# DAP-Peripherals-4.net
KiCad netlist of a schematic drawn in Altium Designer
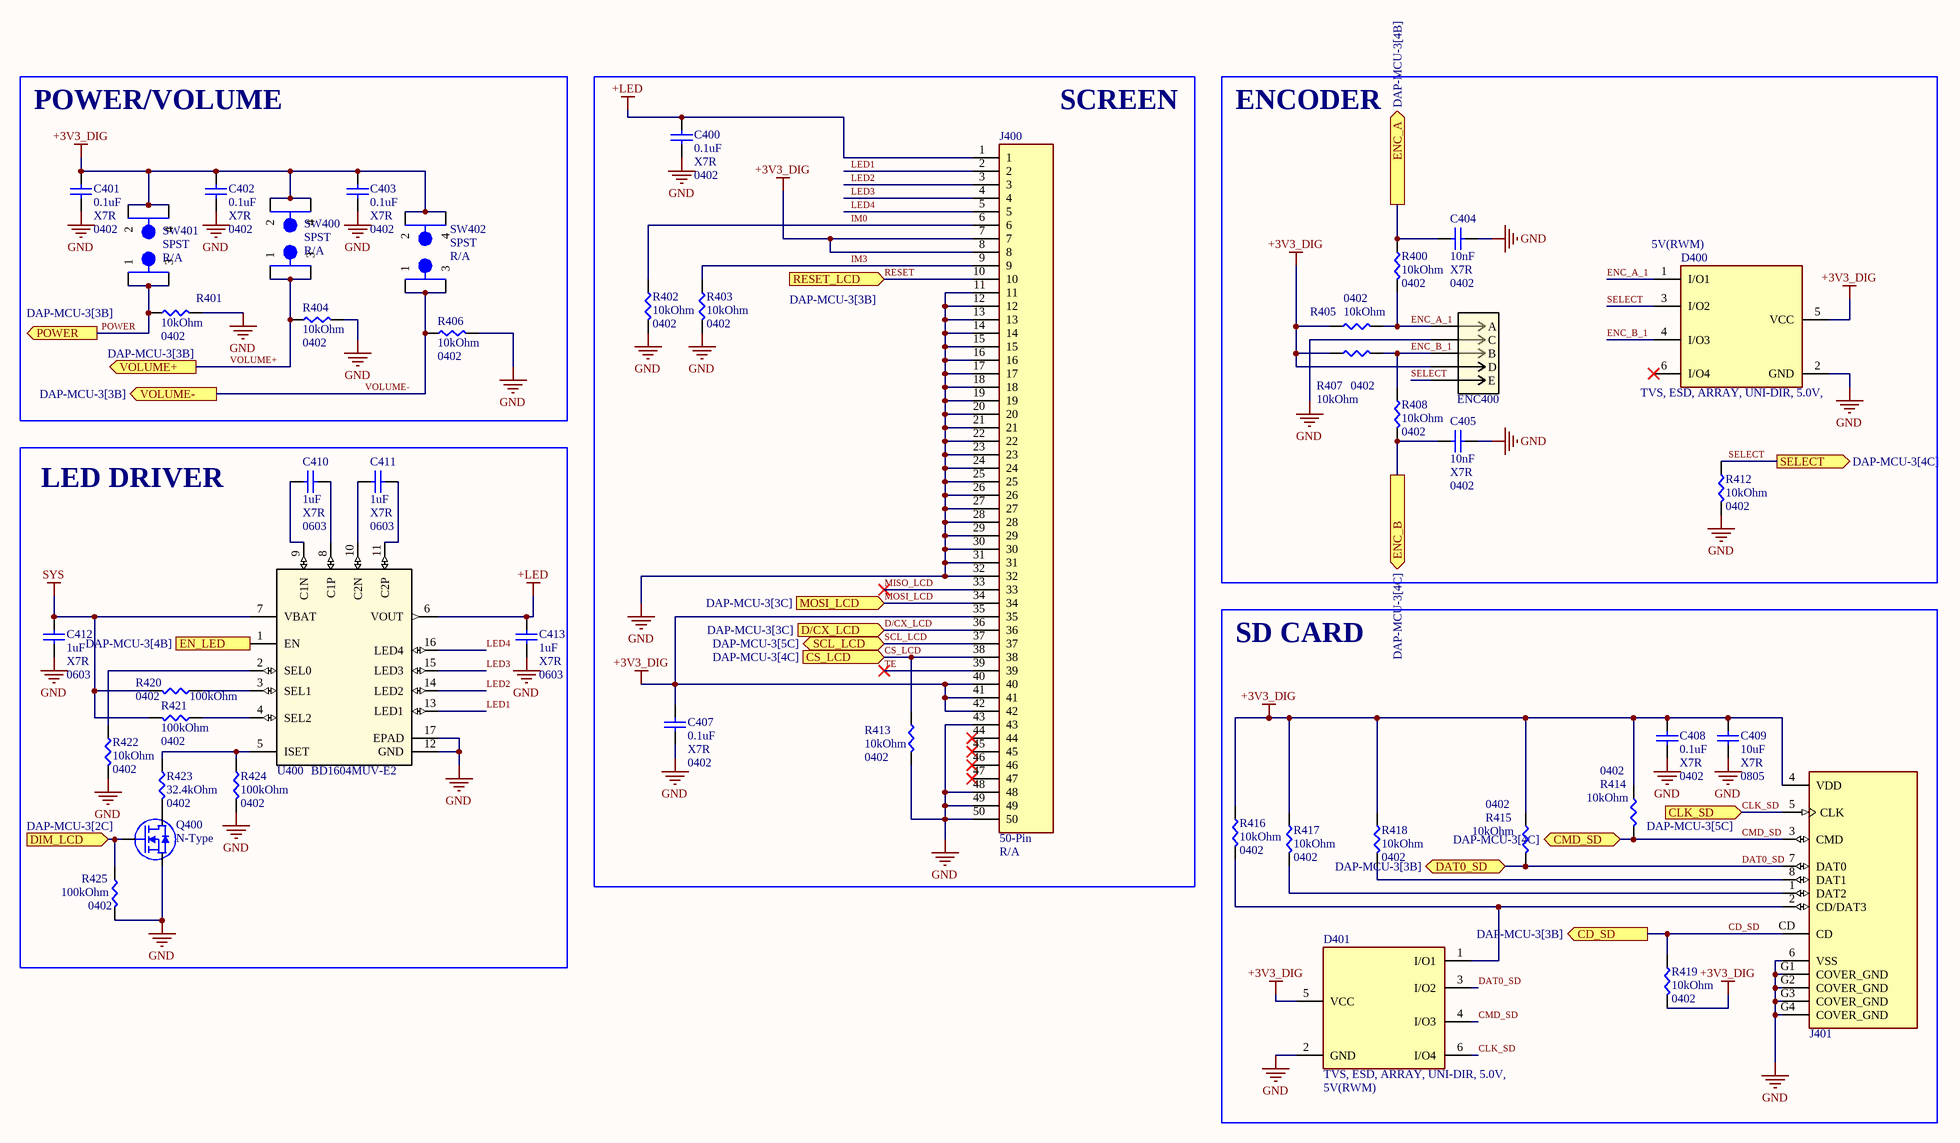
[diagram p0: DAP-Peripherals-4.SchDoc]

(export (version "E")
  (design (tool "Eeschema 10.0.6"))
  (components
    (comp (ref "C400")
      (value "CAP CER 0.1UF 50V X7R 0402")
      (footprint "CAPC1005X60N")
      (fields
        (field (name "<VALUE>") "0.1uF")
        (field (name "<SPEC>") "X7R")
        (field (name "<FOOTPRINT>") "0402")
        (field (name "CREATOR PROJECT") "DAP")
      )
      (libsource (lib "aloker-Link") (part "CAP"))
    )
    (comp (ref "C401")
      (value "CAP CER 0.1UF 50V X7R 0402")
      (footprint "CAPC1005X60N")
      (fields
        (field (name "<VALUE>") "0.1uF")
        (field (name "<SPEC>") "X7R")
        (field (name "<FOOTPRINT>") "0402")
        (field (name "CREATOR PROJECT") "DAP")
      )
      (libsource (lib "aloker-Link") (part "CAP"))
    )
    (comp (ref "C402")
      (value "CAP CER 0.1UF 50V X7R 0402")
      (footprint "CAPC1005X60N")
      (fields
        (field (name "<VALUE>") "0.1uF")
        (field (name "<SPEC>") "X7R")
        (field (name "<FOOTPRINT>") "0402")
        (field (name "CREATOR PROJECT") "DAP")
      )
      (libsource (lib "aloker-Link") (part "CAP"))
    )
    (comp (ref "C403")
      (value "CAP CER 0.1UF 50V X7R 0402")
      (footprint "CAPC1005X60N")
      (fields
        (field (name "<VALUE>") "0.1uF")
        (field (name "<SPEC>") "X7R")
        (field (name "<FOOTPRINT>") "0402")
        (field (name "CREATOR PROJECT") "DAP")
      )
      (libsource (lib "aloker-Link") (part "CAP"))
    )
    (comp (ref "C404")
      (value "CAP CER 10000PF 16V X7R 0402")
      (footprint "CAPC1005X55N")
      (fields
        (field (name "<VALUE>") "10nF")
        (field (name "<SPEC>") "X7R")
        (field (name "<FOOTPRINT>") "0402")
        (field (name "CREATOR PROJECT") "aRTy")
      )
      (libsource (lib "aloker-Link") (part "CAP"))
    )
    (comp (ref "C405")
      (value "CAP CER 10000PF 16V X7R 0402")
      (footprint "CAPC1005X55N")
      (fields
        (field (name "<VALUE>") "10nF")
        (field (name "<SPEC>") "X7R")
        (field (name "<FOOTPRINT>") "0402")
        (field (name "CREATOR PROJECT") "aRTy")
      )
      (libsource (lib "aloker-Link") (part "CAP"))
    )
    (comp (ref "C407")
      (value "CAP CER 0.1UF 50V X7R 0402")
      (footprint "CAPC1005X60N")
      (fields
        (field (name "<VALUE>") "0.1uF")
        (field (name "<SPEC>") "X7R")
        (field (name "<FOOTPRINT>") "0402")
        (field (name "CREATOR PROJECT") "DAP")
      )
      (libsource (lib "aloker-Link") (part "CAP"))
    )
    (comp (ref "C408")
      (value "CAP CER 0.1UF 50V X7R 0402")
      (footprint "CAPC1005X60N")
      (fields
        (field (name "<VALUE>") "0.1uF")
        (field (name "<SPEC>") "X7R")
        (field (name "<FOOTPRINT>") "0402")
        (field (name "CREATOR PROJECT") "DAP")
      )
      (libsource (lib "aloker-Link") (part "CAP"))
    )
    (comp (ref "C409")
      (value "CAP CER 10UF 10V X7R 0805")
      (footprint "CAPC2012X140N")
      (fields
        (field (name "<VALUE>") "10uF")
        (field (name "<SPEC>") "X7R")
        (field (name "<FOOTPRINT>") "0805")
        (field (name "CREATOR PROJECT") "DAP")
      )
      (libsource (lib "aloker-Link") (part "CAP"))
    )
    (comp (ref "C410")
      (value "CAP CER 1UF 25V X7R 0603")
      (footprint "CAPC1608X100N")
      (fields
        (field (name "<VALUE>") "1uF")
        (field (name "<SPEC>") "X7R")
        (field (name "<FOOTPRINT>") "0603")
        (field (name "CREATOR PROJECT") "DAP")
      )
      (libsource (lib "aloker-Link") (part "CAP"))
    )
    (comp (ref "C411")
      (value "CAP CER 1UF 25V X7R 0603")
      (footprint "CAPC1608X100N")
      (fields
        (field (name "<VALUE>") "1uF")
        (field (name "<SPEC>") "X7R")
        (field (name "<FOOTPRINT>") "0603")
        (field (name "CREATOR PROJECT") "DAP")
      )
      (libsource (lib "aloker-Link") (part "CAP"))
    )
    (comp (ref "C412")
      (value "CAP CER 1UF 25V X7R 0603")
      (footprint "CAPC1608X100N")
      (fields
        (field (name "<VALUE>") "1uF")
        (field (name "<SPEC>") "X7R")
        (field (name "<FOOTPRINT>") "0603")
        (field (name "CREATOR PROJECT") "DAP")
      )
      (libsource (lib "aloker-Link") (part "CAP"))
    )
    (comp (ref "C413")
      (value "CAP CER 1UF 25V X7R 0603")
      (footprint "CAPC1608X100N")
      (fields
        (field (name "<VALUE>") "1uF")
        (field (name "<SPEC>") "X7R")
        (field (name "<FOOTPRINT>") "0603")
        (field (name "CREATOR PROJECT") "DAP")
      )
      (libsource (lib "aloker-Link") (part "CAP"))
    )
    (comp (ref "D400")
      (value "TVS, ESD, ARRAY, UNI-DIR, 5.0V,")
      (footprint "TVS_ARR_4UNI_FP")
      (fields (field (name "<VALUE>") "5V(RWM)") (field (name "CREATOR PROJECT") "DAP"))
      (libsource (lib "aloker-Link") (part "TVS_ARR_4UNI"))
    )
    (comp (ref "D401")
      (value "TVS, ESD, ARRAY, UNI-DIR, 5.0V,")
      (footprint "TVS_ARR_4UNI_FP")
      (fields (field (name "<VALUE>") "5V(RWM)") (field (name "CREATOR PROJECT") "DAP"))
      (libsource (lib "") (part "TVS_ARR_4UNI_1"))
    )
    (comp (ref "ENC400")
      (value "ENCODER MECH QUAD RGH ANG PC PIN")
      (footprint "EN12-VS_TTE")
      (fields (field (name "CREATOR PROJECT") "DAP"))
      (libsource (lib "aloker-Link") (part "ENC_SWITCH"))
    )
    (comp (ref "J400")
      (value "CONN FFC BOTTOM 50POS 0.5MM R/A")
      (footprint "AMPHENOL_F32D-1A7Y1-21050")
      (fields
        (field (name "MF") "Amphenol ICC (FCI)")
        (field (name "MP") "F32D-1A7Y1-21050")
        (field (name "<VALUE>") "50-Pin")
        (field (name "<FOOTPRINT>") "R/A")
        (field (name "CREATOR PROJECT") "DAP")
      )
      (libsource (lib "aloker-Link") (part "F32D-1A7Y1-21050"))
    )
    (comp (ref "J401")
      (value "CONN MICROSD CARD R/A SMD")
      (footprint "CUI_MSD-1-A")
      (fields
        (field (name "MF") "Same Sky")
        (field (name "MP") "MSD-1-A")
        (field (name "CREATOR PROJECT") "DAP")
      )
      (libsource (lib "aloker-Link") (part "MSD-1-A"))
    )
    (comp (ref "Q400")
      (value "MOSFET N-CH 60V 115MA SOT23")
      (footprint "SOT-23_MCC")
      (fields
        (field (name "MF") "Micro Commercial")
        (field (name "MP") "2N7002-TP")
        (field (name "<VALUE>") "N-Type")
        (field (name "CREATOR PROJECT") "DAP")
      )
      (libsource (lib "aloker-Link") (part "N-MOSFET"))
    )
    (comp (ref "R400")
      (value "RES SMD 10K OHM 1% 1/16W 0402")
      (footprint "RESC1005X40N")
      (fields
        (field (name "<VALUE>") "10kOhm")
        (field (name "<FOOTPRINT>") "0402")
        (field (name "CREATOR PROJECT") "DAP")
      )
      (libsource (lib "aloker-Link") (part "RES"))
    )
    (comp (ref "R401")
      (value "RES SMD 10K OHM 1% 1/16W 0402")
      (footprint "RESC1005X40N")
      (fields
        (field (name "<VALUE>") "10kOhm")
        (field (name "<FOOTPRINT>") "0402")
        (field (name "CREATOR PROJECT") "DAP")
      )
      (libsource (lib "aloker-Link") (part "RES"))
    )
    (comp (ref "R402")
      (value "RES SMD 10K OHM 1% 1/16W 0402")
      (footprint "RESC1005X40N")
      (fields
        (field (name "<VALUE>") "10kOhm")
        (field (name "<FOOTPRINT>") "0402")
        (field (name "CREATOR PROJECT") "DAP")
      )
      (libsource (lib "aloker-Link") (part "RES"))
    )
    (comp (ref "R403")
      (value "RES SMD 10K OHM 1% 1/16W 0402")
      (footprint "RESC1005X40N")
      (fields
        (field (name "<VALUE>") "10kOhm")
        (field (name "<FOOTPRINT>") "0402")
        (field (name "CREATOR PROJECT") "DAP")
      )
      (libsource (lib "aloker-Link") (part "RES"))
    )
    (comp (ref "R404")
      (value "RES SMD 10K OHM 1% 1/16W 0402")
      (footprint "RESC1005X40N")
      (fields
        (field (name "<VALUE>") "10kOhm")
        (field (name "<FOOTPRINT>") "0402")
        (field (name "CREATOR PROJECT") "DAP")
      )
      (libsource (lib "aloker-Link") (part "RES"))
    )
    (comp (ref "R405")
      (value "RES SMD 10K OHM 1% 1/16W 0402")
      (footprint "RESC1005X40N")
      (fields
        (field (name "<VALUE>") "10kOhm")
        (field (name "<FOOTPRINT>") "0402")
        (field (name "CREATOR PROJECT") "DAP")
      )
      (libsource (lib "aloker-Link") (part "RES"))
    )
    (comp (ref "R406")
      (value "RES SMD 10K OHM 1% 1/16W 0402")
      (footprint "RESC1005X40N")
      (fields
        (field (name "<VALUE>") "10kOhm")
        (field (name "<FOOTPRINT>") "0402")
        (field (name "CREATOR PROJECT") "DAP")
      )
      (libsource (lib "aloker-Link") (part "RES"))
    )
    (comp (ref "R407")
      (value "RES SMD 10K OHM 1% 1/16W 0402")
      (footprint "RESC1005X40N")
      (fields
        (field (name "<VALUE>") "10kOhm")
        (field (name "<FOOTPRINT>") "0402")
        (field (name "CREATOR PROJECT") "DAP")
      )
      (libsource (lib "aloker-Link") (part "RES"))
    )
    (comp (ref "R408")
      (value "RES SMD 10K OHM 1% 1/16W 0402")
      (footprint "RESC1005X40N")
      (fields
        (field (name "<VALUE>") "10kOhm")
        (field (name "<FOOTPRINT>") "0402")
        (field (name "CREATOR PROJECT") "DAP")
      )
      (libsource (lib "aloker-Link") (part "RES"))
    )
    (comp (ref "R412")
      (value "RES SMD 10K OHM 1% 1/16W 0402")
      (footprint "RESC1005X40N")
      (fields
        (field (name "<VALUE>") "10kOhm")
        (field (name "<FOOTPRINT>") "0402")
        (field (name "CREATOR PROJECT") "DAP")
      )
      (libsource (lib "aloker-Link") (part "RES"))
    )
    (comp (ref "R413")
      (value "RES SMD 10K OHM 1% 1/16W 0402")
      (footprint "RESC1005X40N")
      (fields
        (field (name "<VALUE>") "10kOhm")
        (field (name "<FOOTPRINT>") "0402")
        (field (name "CREATOR PROJECT") "DAP")
      )
      (libsource (lib "aloker-Link") (part "RES"))
    )
    (comp (ref "R414")
      (value "RES SMD 10K OHM 1% 1/16W 0402")
      (footprint "RESC1005X40N")
      (fields
        (field (name "<VALUE>") "10kOhm")
        (field (name "<FOOTPRINT>") "0402")
        (field (name "CREATOR PROJECT") "DAP")
      )
      (libsource (lib "aloker-Link") (part "RES"))
    )
    (comp (ref "R415")
      (value "RES SMD 10K OHM 1% 1/16W 0402")
      (footprint "RESC1005X40N")
      (fields
        (field (name "<VALUE>") "10kOhm")
        (field (name "<FOOTPRINT>") "0402")
        (field (name "CREATOR PROJECT") "DAP")
      )
      (libsource (lib "aloker-Link") (part "RES"))
    )
    (comp (ref "R416")
      (value "RES SMD 10K OHM 1% 1/16W 0402")
      (footprint "RESC1005X40N")
      (fields
        (field (name "<VALUE>") "10kOhm")
        (field (name "<FOOTPRINT>") "0402")
        (field (name "CREATOR PROJECT") "DAP")
      )
      (libsource (lib "aloker-Link") (part "RES"))
    )
    (comp (ref "R417")
      (value "RES SMD 10K OHM 1% 1/16W 0402")
      (footprint "RESC1005X40N")
      (fields
        (field (name "<VALUE>") "10kOhm")
        (field (name "<FOOTPRINT>") "0402")
        (field (name "CREATOR PROJECT") "DAP")
      )
      (libsource (lib "aloker-Link") (part "RES"))
    )
    (comp (ref "R418")
      (value "RES SMD 10K OHM 1% 1/16W 0402")
      (footprint "RESC1005X40N")
      (fields
        (field (name "<VALUE>") "10kOhm")
        (field (name "<FOOTPRINT>") "0402")
        (field (name "CREATOR PROJECT") "DAP")
      )
      (libsource (lib "aloker-Link") (part "RES"))
    )
    (comp (ref "R419")
      (value "RES SMD 10K OHM 1% 1/16W 0402")
      (footprint "RESC1005X40N")
      (fields
        (field (name "<VALUE>") "10kOhm")
        (field (name "<FOOTPRINT>") "0402")
        (field (name "CREATOR PROJECT") "DAP")
      )
      (libsource (lib "aloker-Link") (part "RES"))
    )
    (comp (ref "R420")
      (value "RES SMD 100K OHM 0.1% 1/16W 0402")
      (footprint "RESC1005X40N")
      (fields
        (field (name "<VALUE>") "100kOhm")
        (field (name "<FOOTPRINT>") "0402")
        (field (name "CREATOR PROJECT") "DAP")
      )
      (libsource (lib "aloker-Link") (part "RES"))
    )
    (comp (ref "R421")
      (value "RES SMD 100K OHM 0.1% 1/16W 0402")
      (footprint "RESC1005X40N")
      (fields
        (field (name "<VALUE>") "100kOhm")
        (field (name "<FOOTPRINT>") "0402")
        (field (name "CREATOR PROJECT") "DAP")
      )
      (libsource (lib "aloker-Link") (part "RES"))
    )
    (comp (ref "R422")
      (value "RES SMD 10K OHM 1% 1/16W 0402")
      (footprint "RESC1005X40N")
      (fields
        (field (name "<VALUE>") "10kOhm")
        (field (name "<FOOTPRINT>") "0402")
        (field (name "CREATOR PROJECT") "DAP")
      )
      (libsource (lib "aloker-Link") (part "RES"))
    )
    (comp (ref "R423")
      (value "RES 32.4K OHM 1% 1/16W 0402")
      (footprint "RESC1005X40N")
      (fields
        (field (name "<VALUE>") "32.4kOhm")
        (field (name "<FOOTPRINT>") "0402")
        (field (name "CREATOR PROJECT") "DAP")
      )
      (libsource (lib "aloker-Link") (part "RES"))
    )
    (comp (ref "R424")
      (value "RES SMD 100K OHM 0.1% 1/16W 0402")
      (footprint "RESC1005X40N")
      (fields
        (field (name "<VALUE>") "100kOhm")
        (field (name "<FOOTPRINT>") "0402")
        (field (name "CREATOR PROJECT") "DAP")
      )
      (libsource (lib "aloker-Link") (part "RES"))
    )
    (comp (ref "R425")
      (value "RES SMD 100K OHM 0.1% 1/16W 0402")
      (footprint "RESC1005X40N")
      (fields
        (field (name "<VALUE>") "100kOhm")
        (field (name "<FOOTPRINT>") "0402")
        (field (name "CREATOR PROJECT") "DAP")
      )
      (libsource (lib "aloker-Link") (part "RES"))
    )
    (comp (ref "SW400")
      (value "SWITCH TACTILE SPST-NO 0.05A 12V")
      (footprint "SW_TL1014BF220QG")
      (fields
        (field (name "<VALUE>") "SPST")
        (field (name "<FOOTPRINT>") "R/A")
        (field (name "CREATOR PROJECT") "DAP")
      )
      (libsource (lib "aloker-Link") (part "SWITCH_SPST"))
    )
    (comp (ref "SW401")
      (value "SWITCH TACTILE SPST-NO 0.05A 12V")
      (footprint "SW_TL1014BF220QG")
      (fields
        (field (name "<VALUE>") "SPST")
        (field (name "<FOOTPRINT>") "R/A")
        (field (name "CREATOR PROJECT") "DAP")
      )
      (libsource (lib "aloker-Link") (part "SWITCH_SPST"))
    )
    (comp (ref "SW402")
      (value "SWITCH TACTILE SPST-NO 0.05A 12V")
      (footprint "SW_TL1014BF220QG")
      (fields
        (field (name "<VALUE>") "SPST")
        (field (name "<FOOTPRINT>") "R/A")
        (field (name "CREATOR PROJECT") "DAP")
      )
      (libsource (lib "aloker-Link") (part "SWITCH_SPST"))
    )
    (comp (ref "U400")
      (value "IC LED DRIVER RGLTR 30MA 16VQFN")
      (footprint "VQFN016V3030_ROM")
      (fields
        (field (name "MANUFACTURER_PART_NUMBER") "BD1604MUV-E2")
        (field (name "MANUFACTURER PART NUMBER 1") "BD1604MUV-E2")
        (field (name "COPYRIGHT") "Copyright (C) 2025 Ultra Librarian. All rights reserved.")
        (field (name "CREATOR PROJECT") "DAP")
      )
      (libsource (lib "aloker-Link") (part "BD1604MUV-E2"))
    )
  )
  (nets
    (net (code "1") (name "+3V3_DIG") (class "Default")
      (node (ref "C401") (pin "2") (pinfunction "2_2") (pintype "passive"))
      (node (ref "C402") (pin "2") (pinfunction "2_2") (pintype "passive"))
      (node (ref "C403") (pin "2") (pinfunction "2_2") (pintype "passive"))
      (node (ref "C407") (pin "2") (pinfunction "2_2") (pintype "passive"))
      (node (ref "C408") (pin "2") (pinfunction "2_2") (pintype "passive"))
      (node (ref "C409") (pin "2") (pinfunction "2_2") (pintype "passive"))
      (node (ref "D400") (pin "5") (pinfunction "VCC_5") (pintype "passive"))
      (node (ref "D401") (pin "5") (pinfunction "VCC_5") (pintype "passive"))
      (node (ref "ENC400") (pin "4") (pinfunction "D_4") (pintype "passive"))
      (node (ref "J400") (pin "35") (pinfunction "35_35") (pintype "passive"))
      (node (ref "J400") (pin "40") (pinfunction "40_40") (pintype "passive"))
      (node (ref "J400") (pin "41") (pinfunction "41_41") (pintype "passive"))
      (node (ref "J400") (pin "42") (pinfunction "42_42") (pintype "passive"))
      (node (ref "J400") (pin "7") (pinfunction "7_7") (pintype "passive"))
      (node (ref "J400") (pin "8") (pinfunction "8_8") (pintype "passive"))
      (node (ref "J401") (pin "4") (pinfunction "VDD_4") (pintype "power_in"))
      (node (ref "R405") (pin "2") (pinfunction "2_2") (pintype "passive"))
      (node (ref "R407") (pin "2") (pinfunction "2_2") (pintype "passive"))
      (node (ref "R414") (pin "2") (pinfunction "2_2") (pintype "passive"))
      (node (ref "R415") (pin "2") (pinfunction "2_2") (pintype "passive"))
      (node (ref "R416") (pin "2") (pinfunction "2_2") (pintype "passive"))
      (node (ref "R417") (pin "2") (pinfunction "2_2") (pintype "passive"))
      (node (ref "R418") (pin "2") (pinfunction "2_2") (pintype "passive"))
      (node (ref "R419") (pin "1") (pinfunction "1_1") (pintype "passive"))
      (node (ref "SW400") (pin "2") (pinfunction "2_2") (pintype "passive"))
      (node (ref "SW400") (pin "4") (pinfunction "4_4") (pintype "passive"))
      (node (ref "SW401") (pin "2") (pinfunction "2_2") (pintype "passive"))
      (node (ref "SW401") (pin "4") (pinfunction "4_4") (pintype "passive"))
      (node (ref "SW402") (pin "2") (pinfunction "2_2") (pintype "passive"))
      (node (ref "SW402") (pin "4") (pinfunction "4_4") (pintype "passive"))
    )
    (net (code "2") (name "+LED") (class "Default")
      (node (ref "C400") (pin "2") (pinfunction "2_2") (pintype "passive"))
      (node (ref "C413") (pin "2") (pinfunction "2_2") (pintype "passive"))
      (node (ref "J400") (pin "1") (pinfunction "1_1") (pintype "passive"))
      (node (ref "U400") (pin "6") (pinfunction "VOUT_6") (pintype "output"))
    )
    (net (code "3") (name "/CD_SD") (class "Default")
      (node (ref "J401") (pin "CD") (pinfunction "CD_CD") (pintype "passive"))
      (node (ref "R419") (pin "2") (pinfunction "2_2") (pintype "passive"))
    )
    (net (code "4") (name "/CLK_SD") (class "Default")
      (node (ref "D401") (pin "6") (pinfunction "I/O4_6") (pintype "passive"))
      (node (ref "J401") (pin "5") (pinfunction "CLK_5") (pintype "input"))
    )
    (net (code "5") (name "/CMD_SD") (class "Default")
      (node (ref "D401") (pin "4") (pinfunction "I/O3_4") (pintype "passive"))
      (node (ref "J401") (pin "3") (pinfunction "CMD_3") (pintype "bidirectional"))
      (node (ref "R414") (pin "1") (pinfunction "1_1") (pintype "passive"))
    )
    (net (code "6") (name "/CS_LCD") (class "Default")
      (node (ref "J400") (pin "38") (pinfunction "38_38") (pintype "passive"))
      (node (ref "R413") (pin "2") (pinfunction "2_2") (pintype "passive"))
    )
    (net (code "7") (name "/DAT0_SD") (class "Default")
      (node (ref "D401") (pin "3") (pinfunction "I/O2_3") (pintype "passive"))
      (node (ref "J401") (pin "7") (pinfunction "DAT0_7") (pintype "bidirectional"))
      (node (ref "R415") (pin "1") (pinfunction "1_1") (pintype "passive"))
    )
    (net (code "8") (name "/DIM_LCD") (class "Default")
      (node (ref "Q400") (pin "1") (pinfunction "G_1") (pintype "passive"))
      (node (ref "R425") (pin "2") (pinfunction "2_2") (pintype "passive"))
    )
    (net (code "9") (name "/D{slash}CX_LCD") (class "Default")
      (node (ref "J400") (pin "36") (pinfunction "36_36") (pintype "passive"))
    )
    (net (code "10") (name "/ENC_A") (class "Default")
      (node (ref "C404") (pin "2") (pinfunction "2_2") (pintype "passive"))
      (node (ref "R400") (pin "2") (pinfunction "2_2") (pintype "passive"))
    )
    (net (code "11") (name "/ENC_A_1") (class "Default")
      (node (ref "D400") (pin "1") (pinfunction "I/O1_1") (pintype "passive"))
      (node (ref "ENC400") (pin "1") (pinfunction "A_1") (pintype "passive"))
      (node (ref "R400") (pin "1") (pinfunction "1_1") (pintype "passive"))
      (node (ref "R405") (pin "1") (pinfunction "1_1") (pintype "passive"))
    )
    (net (code "12") (name "/ENC_B") (class "Default")
      (node (ref "C405") (pin "2") (pinfunction "2_2") (pintype "passive"))
      (node (ref "R408") (pin "1") (pinfunction "1_1") (pintype "passive"))
    )
    (net (code "13") (name "/ENC_B_1") (class "Default")
      (node (ref "D400") (pin "4") (pinfunction "I/O3_4") (pintype "passive"))
      (node (ref "ENC400") (pin "3") (pinfunction "B_3") (pintype "passive"))
      (node (ref "R407") (pin "1") (pinfunction "1_1") (pintype "passive"))
      (node (ref "R408") (pin "2") (pinfunction "2_2") (pintype "passive"))
    )
    (net (code "14") (name "/EN_LED") (class "Default")
      (node (ref "U400") (pin "1") (pinfunction "EN_1") (pintype "passive"))
    )
    (net (code "15") (name "/IM0") (class "Default")
      (node (ref "J400") (pin "6") (pinfunction "6_6") (pintype "passive"))
      (node (ref "R402") (pin "2") (pinfunction "2_2") (pintype "passive"))
    )
    (net (code "16") (name "/IM3") (class "Default")
      (node (ref "J400") (pin "9") (pinfunction "9_9") (pintype "passive"))
      (node (ref "R403") (pin "2") (pinfunction "2_2") (pintype "passive"))
    )
    (net (code "17") (name "/LED1") (class "Default")
      (node (ref "J400") (pin "2") (pinfunction "2_2") (pintype "passive"))
      (node (ref "U400") (pin "13") (pinfunction "LED1_13") (pintype "bidirectional"))
    )
    (net (code "18") (name "/LED2") (class "Default")
      (node (ref "J400") (pin "3") (pinfunction "3_3") (pintype "passive"))
      (node (ref "U400") (pin "14") (pinfunction "LED2_14") (pintype "bidirectional"))
    )
    (net (code "19") (name "/LED3") (class "Default")
      (node (ref "J400") (pin "4") (pinfunction "4_4") (pintype "passive"))
      (node (ref "U400") (pin "15") (pinfunction "LED3_15") (pintype "bidirectional"))
    )
    (net (code "20") (name "/LED4") (class "Default")
      (node (ref "J400") (pin "5") (pinfunction "5_5") (pintype "passive"))
      (node (ref "U400") (pin "16") (pinfunction "LED4_16") (pintype "bidirectional"))
    )
    (net (code "21") (name "/MISO_LCD") (class "Default")
      (node (ref "J400") (pin "33") (pinfunction "33_33") (pintype "passive+no_connect"))
    )
    (net (code "22") (name "/MOSI_LCD") (class "Default")
      (node (ref "J400") (pin "34") (pinfunction "34_34") (pintype "passive"))
    )
    (net (code "23") (name "/POWER") (class "Default")
      (node (ref "R401") (pin "2") (pinfunction "2_2") (pintype "passive"))
      (node (ref "SW401") (pin "1") (pinfunction "1_1") (pintype "passive"))
      (node (ref "SW401") (pin "3") (pinfunction "3_3") (pintype "passive"))
    )
    (net (code "24") (name "/RESET") (class "Default")
      (node (ref "J400") (pin "10") (pinfunction "10_10") (pintype "passive"))
    )
    (net (code "25") (name "/SCL_LCD") (class "Default")
      (node (ref "J400") (pin "37") (pinfunction "37_37") (pintype "passive"))
    )
    (net (code "26") (name "/SELECT") (class "Default")
      (node (ref "D400") (pin "3") (pinfunction "I/O2_3") (pintype "passive"))
      (node (ref "ENC400") (pin "5") (pinfunction "E_5") (pintype "passive"))
      (node (ref "R412") (pin "2") (pinfunction "2_2") (pintype "passive"))
    )
    (net (code "27") (name "/TE") (class "Default")
      (node (ref "J400") (pin "39") (pinfunction "39_39") (pintype "passive+no_connect"))
    )
    (net (code "28") (name "/VOLUME+") (class "Default")
      (node (ref "R404") (pin "2") (pinfunction "2_2") (pintype "passive"))
      (node (ref "SW400") (pin "1") (pinfunction "1_1") (pintype "passive"))
      (node (ref "SW400") (pin "3") (pinfunction "3_3") (pintype "passive"))
    )
    (net (code "29") (name "/VOLUME-") (class "Default")
      (node (ref "R406") (pin "2") (pinfunction "2_2") (pintype "passive"))
      (node (ref "SW402") (pin "1") (pinfunction "1_1") (pintype "passive"))
      (node (ref "SW402") (pin "3") (pinfunction "3_3") (pintype "passive"))
    )
    (net (code "30") (name "GND") (class "Default")
      (node (ref "C400") (pin "1") (pinfunction "1_1") (pintype "passive"))
      (node (ref "C401") (pin "1") (pinfunction "1_1") (pintype "passive"))
      (node (ref "C402") (pin "1") (pinfunction "1_1") (pintype "passive"))
      (node (ref "C403") (pin "1") (pinfunction "1_1") (pintype "passive"))
      (node (ref "C404") (pin "1") (pinfunction "1_1") (pintype "passive"))
      (node (ref "C405") (pin "1") (pinfunction "1_1") (pintype "passive"))
      (node (ref "C407") (pin "1") (pinfunction "1_1") (pintype "passive"))
      (node (ref "C408") (pin "1") (pinfunction "1_1") (pintype "passive"))
      (node (ref "C409") (pin "1") (pinfunction "1_1") (pintype "passive"))
      (node (ref "C412") (pin "1") (pinfunction "1_1") (pintype "passive"))
      (node (ref "C413") (pin "1") (pinfunction "1_1") (pintype "passive"))
      (node (ref "D400") (pin "2") (pinfunction "GND_2") (pintype "passive"))
      (node (ref "D401") (pin "2") (pinfunction "GND_2") (pintype "passive"))
      (node (ref "ENC400") (pin "2") (pinfunction "C_2") (pintype "passive"))
      (node (ref "J400") (pin "11") (pinfunction "11_11") (pintype "passive"))
      (node (ref "J400") (pin "12") (pinfunction "12_12") (pintype "passive"))
      (node (ref "J400") (pin "13") (pinfunction "13_13") (pintype "passive"))
      (node (ref "J400") (pin "14") (pinfunction "14_14") (pintype "passive"))
      (node (ref "J400") (pin "15") (pinfunction "15_15") (pintype "passive"))
      (node (ref "J400") (pin "16") (pinfunction "16_16") (pintype "passive"))
      (node (ref "J400") (pin "17") (pinfunction "17_17") (pintype "passive"))
      (node (ref "J400") (pin "18") (pinfunction "18_18") (pintype "passive"))
      (node (ref "J400") (pin "19") (pinfunction "19_19") (pintype "passive"))
      (node (ref "J400") (pin "20") (pinfunction "20_20") (pintype "passive"))
      (node (ref "J400") (pin "21") (pinfunction "21_21") (pintype "passive"))
      (node (ref "J400") (pin "22") (pinfunction "22_22") (pintype "passive"))
      (node (ref "J400") (pin "23") (pinfunction "23_23") (pintype "passive"))
      (node (ref "J400") (pin "24") (pinfunction "24_24") (pintype "passive"))
      (node (ref "J400") (pin "25") (pinfunction "25_25") (pintype "passive"))
      (node (ref "J400") (pin "26") (pinfunction "26_26") (pintype "passive"))
      (node (ref "J400") (pin "27") (pinfunction "27_27") (pintype "passive"))
      (node (ref "J400") (pin "28") (pinfunction "28_28") (pintype "passive"))
      (node (ref "J400") (pin "29") (pinfunction "29_29") (pintype "passive"))
      (node (ref "J400") (pin "30") (pinfunction "30_30") (pintype "passive"))
      (node (ref "J400") (pin "31") (pinfunction "31_31") (pintype "passive"))
      (node (ref "J400") (pin "32") (pinfunction "32_32") (pintype "passive"))
      (node (ref "J400") (pin "43") (pinfunction "43_43") (pintype "passive"))
      (node (ref "J400") (pin "48") (pinfunction "48_48") (pintype "passive"))
      (node (ref "J400") (pin "49") (pinfunction "49_49") (pintype "passive"))
      (node (ref "J400") (pin "50") (pinfunction "50_50") (pintype "passive"))
      (node (ref "J401") (pin "6") (pinfunction "VSS_6") (pintype "power_in"))
      (node (ref "J401") (pin "G1") (pinfunction "COVER_GND_G1") (pintype "power_in"))
      (node (ref "J401") (pin "G2") (pinfunction "COVER_GND_G2") (pintype "power_in"))
      (node (ref "J401") (pin "G3") (pinfunction "COVER_GND_G3") (pintype "power_in"))
      (node (ref "J401") (pin "G4") (pinfunction "COVER_GND_G4") (pintype "power_in"))
      (node (ref "Q400") (pin "2") (pinfunction "S_2") (pintype "passive"))
      (node (ref "R401") (pin "1") (pinfunction "1_1") (pintype "passive"))
      (node (ref "R402") (pin "1") (pinfunction "1_1") (pintype "passive"))
      (node (ref "R403") (pin "1") (pinfunction "1_1") (pintype "passive"))
      (node (ref "R404") (pin "1") (pinfunction "1_1") (pintype "passive"))
      (node (ref "R406") (pin "1") (pinfunction "1_1") (pintype "passive"))
      (node (ref "R412") (pin "1") (pinfunction "1_1") (pintype "passive"))
      (node (ref "R413") (pin "1") (pinfunction "1_1") (pintype "passive"))
      (node (ref "R422") (pin "1") (pinfunction "1_1") (pintype "passive"))
      (node (ref "R424") (pin "1") (pinfunction "1_1") (pintype "passive"))
      (node (ref "R425") (pin "1") (pinfunction "1_1") (pintype "passive"))
      (node (ref "U400") (pin "12") (pinfunction "GND_12") (pintype "power_in"))
      (node (ref "U400") (pin "17") (pinfunction "EPAD_17") (pintype "passive"))
    )
    (net (code "31") (name "Net-(D401-I{slash}O1)") (class "Default")
      (node (ref "D401") (pin "1") (pinfunction "I/O1_1") (pintype "passive"))
      (node (ref "J401") (pin "2") (pinfunction "CD/DAT3_2") (pintype "bidirectional"))
      (node (ref "R416") (pin "1") (pinfunction "1_1") (pintype "passive"))
    )
    (net (code "32") (name "Net-(J401-DAT1)") (class "Default")
      (node (ref "J401") (pin "8") (pinfunction "DAT1_8") (pintype "bidirectional"))
      (node (ref "R418") (pin "1") (pinfunction "1_1") (pintype "passive"))
    )
    (net (code "33") (name "Net-(J401-DAT2)") (class "Default")
      (node (ref "J401") (pin "1") (pinfunction "DAT2_1") (pintype "bidirectional"))
      (node (ref "R417") (pin "1") (pinfunction "1_1") (pintype "passive"))
    )
    (net (code "34") (name "Net-(Q400-D)") (class "Default")
      (node (ref "Q400") (pin "3") (pinfunction "D_3") (pintype "passive"))
      (node (ref "R423") (pin "1") (pinfunction "1_1") (pintype "passive"))
    )
    (net (code "35") (name "Net-(U400-C1N)") (class "Default")
      (node (ref "C410") (pin "2") (pinfunction "2_2") (pintype "passive"))
      (node (ref "U400") (pin "9") (pinfunction "C1N_9") (pintype "bidirectional"))
    )
    (net (code "36") (name "Net-(U400-C1P)") (class "Default")
      (node (ref "C410") (pin "1") (pinfunction "1_1") (pintype "passive"))
      (node (ref "U400") (pin "8") (pinfunction "C1P_8") (pintype "bidirectional"))
    )
    (net (code "37") (name "Net-(U400-C2N)") (class "Default")
      (node (ref "C411") (pin "2") (pinfunction "2_2") (pintype "passive"))
      (node (ref "U400") (pin "10") (pinfunction "C2N_10") (pintype "bidirectional"))
    )
    (net (code "38") (name "Net-(U400-C2P)") (class "Default")
      (node (ref "C411") (pin "1") (pinfunction "1_1") (pintype "passive"))
      (node (ref "U400") (pin "11") (pinfunction "C2P_11") (pintype "bidirectional"))
    )
    (net (code "39") (name "Net-(U400-ISET)") (class "Default")
      (node (ref "R423") (pin "2") (pinfunction "2_2") (pintype "passive"))
      (node (ref "R424") (pin "2") (pinfunction "2_2") (pintype "passive"))
      (node (ref "U400") (pin "5") (pinfunction "ISET_5") (pintype "passive"))
    )
    (net (code "40") (name "Net-(U400-SEL0)") (class "Default")
      (node (ref "R422") (pin "2") (pinfunction "2_2") (pintype "passive"))
      (node (ref "U400") (pin "2") (pinfunction "SEL0_2") (pintype "bidirectional"))
    )
    (net (code "41") (name "Net-(U400-SEL1)") (class "Default")
      (node (ref "R420") (pin "2") (pinfunction "2_2") (pintype "passive"))
      (node (ref "U400") (pin "3") (pinfunction "SEL1_3") (pintype "bidirectional"))
    )
    (net (code "42") (name "Net-(U400-SEL2)") (class "Default")
      (node (ref "R421") (pin "2") (pinfunction "2_2") (pintype "passive"))
      (node (ref "U400") (pin "4") (pinfunction "SEL2_4") (pintype "bidirectional"))
    )
    (net (code "43") (name "SYS") (class "Default")
      (node (ref "C412") (pin "2") (pinfunction "2_2") (pintype "passive"))
      (node (ref "R420") (pin "1") (pinfunction "1_1") (pintype "passive"))
      (node (ref "R421") (pin "1") (pinfunction "1_1") (pintype "passive"))
      (node (ref "U400") (pin "7") (pinfunction "VBAT_7") (pintype "passive"))
    )
    (net (code "44") (name "unconnected-(D400-I{slash}O4-Pad6)") (class "Default")
      (node (ref "D400") (pin "6") (pinfunction "I/O4_6") (pintype "passive+no_connect"))
    )
    (net (code "45") (name "unconnected-(J400-Pad44)") (class "Default")
      (node (ref "J400") (pin "44") (pinfunction "44_44") (pintype "passive+no_connect"))
    )
    (net (code "46") (name "unconnected-(J400-Pad45)") (class "Default")
      (node (ref "J400") (pin "45") (pinfunction "45_45") (pintype "passive+no_connect"))
    )
    (net (code "47") (name "unconnected-(J400-Pad46)") (class "Default")
      (node (ref "J400") (pin "46") (pinfunction "46_46") (pintype "passive+no_connect"))
    )
    (net (code "48") (name "unconnected-(J400-Pad47)") (class "Default")
      (node (ref "J400") (pin "47") (pinfunction "47_47") (pintype "passive+no_connect"))
    )
  )
)
